# power.net
KiCad netlist of a schematic drawn in Altium Designer
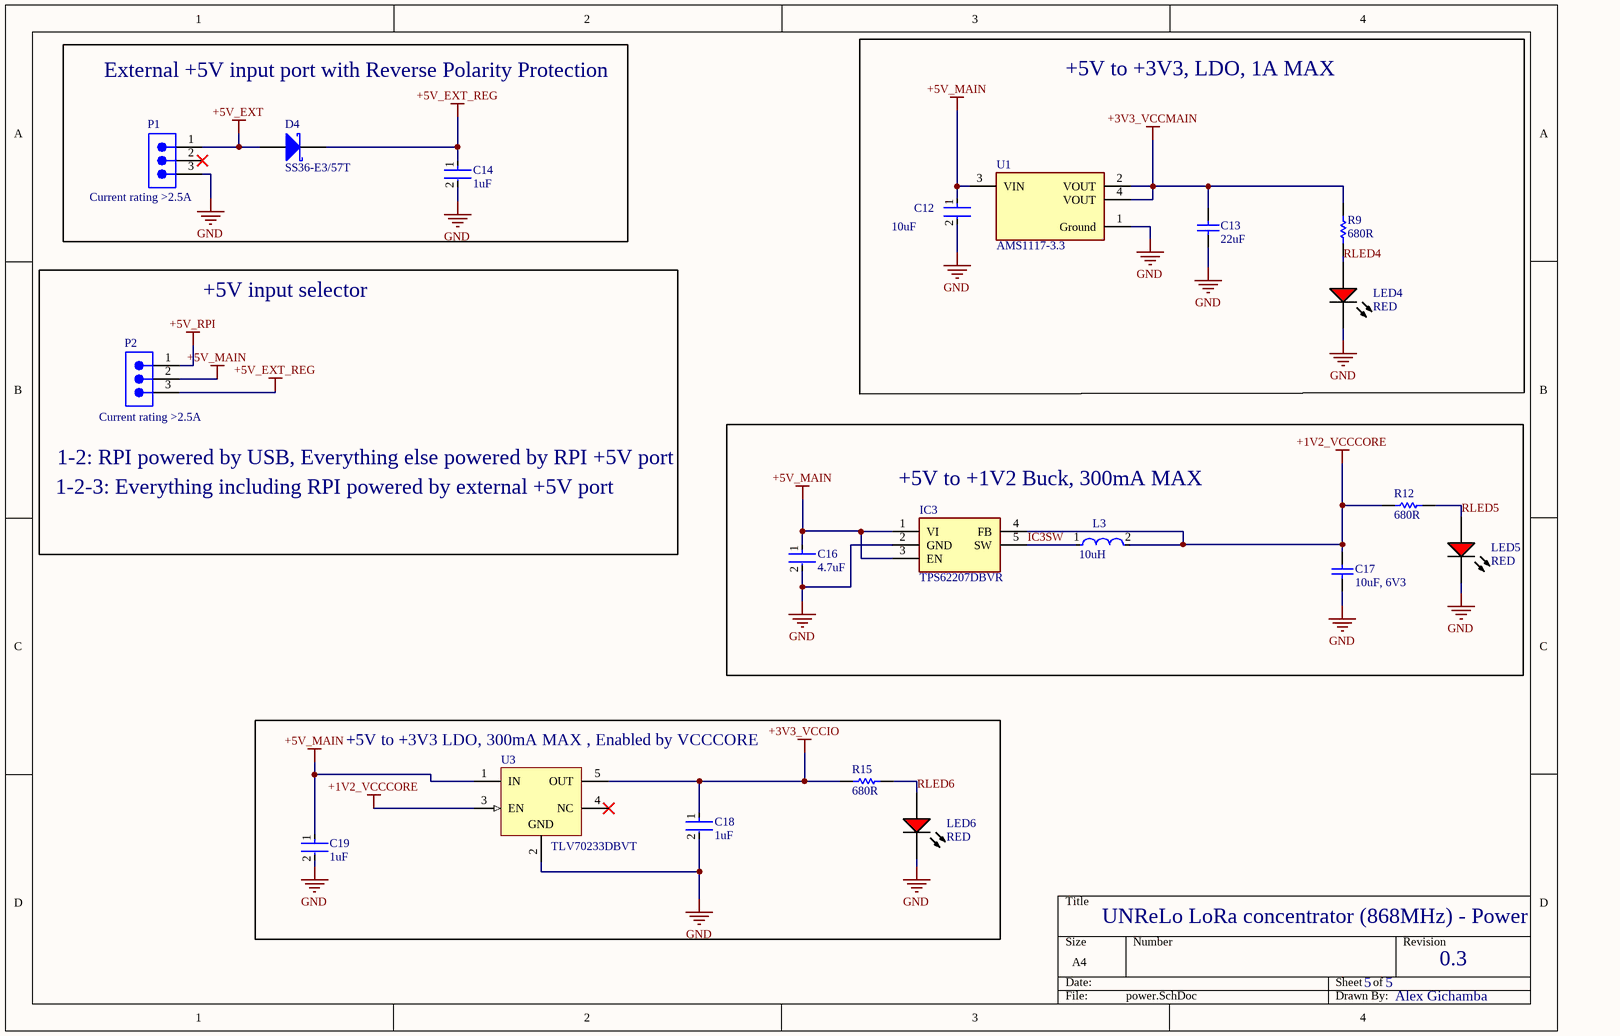
[diagram p0: power.SchDoc]

(export (version "E")
  (design (tool "Eeschema 10.0.6"))
  (components
    (comp (ref "C12")
      (value "10uF")
      (footprint "FP-CL10-IPC_A")
      (description "Cap Ceramic 10uF 6.3V X5R ±20% Pad SMD 0603 +85°C T/R")
      (fields (field (name "VOLTAGE") "6.3V") (field (name "TOLERANCE") "20%"))
      (libsource (lib "Altium Content Vault") (part "b4654b650e69147ec39a6b967a45e02"))
    )
    (comp (ref "C13")
      (value "22uF")
      (footprint "CAPC2013X140X45LL15T25")
      (description "Multi-layer Ceramic Capacitor, 22 uF, -55 to 85 degC, 2-Pin SMD (0805), RoHS, Tape and Reel")
      (fields (field (name "MANUFACTURER") "Samsung Electro-Mechanics") (field (name "TOLERANCE") "±20%"))
      (libsource (lib "Altium Content Vault") (part "CAP-NP-2"))
    )
    (comp (ref "C14")
      (value "1uF")
      (footprint "FP-CL21-IPC_A")
      (description "CL21 Series 0805 1uF 16V ±10% Tolerance X7R Multilayer Ceramic Chip Capacitor")
      (fields (field (name "TOLERANCE") "10%") (field (name "VOLTAGE") "16V"))
      (libsource (lib "Altium Content Vault") (part "b4654b650e69147ec39a6b967a45e02"))
    )
    (comp (ref "C16")
      (value "4.7uF")
      (footprint "FP-CL21-IPC_A")
      (description "CL21 Series 0805 4.7uF 25V ±10% Tolerance X5R Multilayer Ceramic Chip Capacitor")
      (fields (field (name "TOLERANCE") "10%"))
      (libsource (lib "Altium Content Vault") (part "b4654b650e69147ec39a6b967a45e02"))
    )
    (comp (ref "C17")
      (value "10uF, 6V3")
      (footprint "CAPC2013X95X50LL10T25")
      (description "Chip Capacitor, 10 uF, +/- 10%, 6.3 V, -55 to 85 degC, 0805 (2012 Metric), RoHS, Tape and Reel")
      (fields (field (name "TOLERANCE") "±10%") (field (name "MANUFACTURER") "Taiyo Yuden"))
      (libsource (lib "Altium Content Vault") (part "CAP-NP-2"))
    )
    (comp (ref "C18")
      (value "1uF")
      (footprint "FP-CL21-IPC_A")
      (description "CL21 Series 0805 1uF 16V ±10% Tolerance X7R Multilayer Ceramic Chip Capacitor")
      (fields (field (name "TOLERANCE") "10%") (field (name "VOLTAGE") "16V"))
      (libsource (lib "Altium Content Vault") (part "b4654b650e69147ec39a6b967a45e02"))
    )
    (comp (ref "C19")
      (value "1uF")
      (footprint "FP-CL21-IPC_A")
      (description "CL21 Series 0805 1uF 16V ±10% Tolerance X7R Multilayer Ceramic Chip Capacitor")
      (fields (field (name "TOLERANCE") "10%") (field (name "VOLTAGE") "16V"))
      (libsource (lib "Altium Content Vault") (part "b4654b650e69147ec39a6b967a45e02"))
    )
    (comp (ref "D4")
      (value "SS36-E3/57T")
      (footprint "VISH-DO-214AB-2_V")
      (fields (field (name "MANUFACTURER") "Vishay"))
      (libsource (lib "Altium Content Vault") (part "DSKY-AK-2"))
    )
    (comp (ref "IC3")
      (value "TPS62207DBVR")
      (footprint "SamacSys:SOT95P280X145-5N")
      (description "Integrated Circuit")
      (fields (field (name "MOUSER PART NUMBER") "595-TPS62207DBVR"))
      (libsource (lib "*") (part "TPS62207DBVR"))
    )
    (comp (ref "L3")
      (value "10uH")
      (footprint "FP-LQH43CN_03-MFG")
      (description "Wire Wound Ferrite Inductor for Power Lines For Automotive 10μH ±20% 0.1764Ω 1170mA 1812")
      (fields (field (name "TOLERANCE") "5%"))
      (libsource (lib "Altium Content Vault") (part "725321dda6339637d4d059423bc1c3c"))
    )
    (comp (ref "LED4")
      (value "RED")
      (footprint "LTST-C170KRKT_V")
      (description "LED Red, 75 mW, 54 mcd, -55 to 85 degC, 2-Pin SMD, RoHS, Tape and Reel")
      (fields (field (name "MANUFACTURER") "Lite-On"))
      (libsource (lib "Altium Content Vault") (part "LED-RED-AK-2"))
    )
    (comp (ref "LED5")
      (value "RED")
      (footprint "LTST-C170KRKT_V")
      (description "LED Red, 75 mW, 54 mcd, -55 to 85 degC, 2-Pin SMD, RoHS, Tape and Reel")
      (fields (field (name "MANUFACTURER") "Lite-On"))
      (libsource (lib "Altium Content Vault") (part "LED-RED-AK-2"))
    )
    (comp (ref "LED6")
      (value "RED")
      (footprint "LTST-C170KRKT_V")
      (description "LED Red, 75 mW, 54 mcd, -55 to 85 degC, 2-Pin SMD, RoHS, Tape and Reel")
      (fields (field (name "MANUFACTURER") "Lite-On"))
      (libsource (lib "Altium Content Vault") (part "LED-RED-AK-2"))
    )
    (comp (ref "P1")
      (value "Current rating >2.5A")
      (footprint "SMTC-TSW-103-07-X-S")
      (description "0.025\" SQ Post Header, Through-hole, Vertical, -55 to 105 degC, 2.54 mm Pitch, 3-Pin, Male, RoHS")
      (fields (field (name "PARTNUMBER") "TSW-103-07-T-S") (field (name "MANUFACTURER") "Samtec"))
      (libsource (lib "Altium Content Vault") (part "SMTC-TSW-103-X-X-S-X"))
    )
    (comp (ref "P2")
      (value "Current rating >2.5A")
      (footprint "SMTC-TSW-103-07-X-S")
      (description "0.025\" SQ Post Header, Through-hole, Vertical, -55 to 105 degC, 2.54 mm Pitch, 3-Pin, Male, RoHS")
      (fields (field (name "PARTNUMBER") "TSW-103-07-T-S") (field (name "MANUFACTURER") "Samtec"))
      (libsource (lib "Altium Content Vault") (part "SMTC-TSW-103-X-X-S-X"))
    )
    (comp (ref "R9")
      (value "680R")
      (footprint "RESC2013X70X40ML20T20")
      (fields (field (name "PART NUMBER") "ERJ6ENF6800V") (field (name "MANUFACTURER") "Panasonic"))
      (libsource (lib "Altium Content Vault") (part "RES"))
    )
    (comp (ref "R12")
      (value "680R")
      (footprint "RESC2013X70X40ML20T20")
      (fields (field (name "PART NUMBER") "ERJ6ENF6800V") (field (name "MANUFACTURER") "Panasonic"))
      (libsource (lib "Altium Content Vault") (part "RES"))
    )
    (comp (ref "R15")
      (value "680R")
      (footprint "RESC2013X70X40ML20T20")
      (fields (field (name "PART NUMBER") "ERJ6ENF6800V") (field (name "MANUFACTURER") "Panasonic"))
      (libsource (lib "Altium Content Vault") (part "RES"))
    )
    (comp (ref "U1")
      (value "AMS1117-3.3")
      (footprint "FP-AMS1117-IPC_C")
      (description "LDO Voltage Regulators 1A, 3.3V")
      (fields
        (field (name "OCTOPART") "https://octopart.com/ams1117-3.3-advanced+monolithic+systems-25899300")
        (field (name "MANUFACTURER") "Advanced Monolithic Systems")
      )
      (libsource (lib "Altium Content Vault") (part "8bdbb5f8e77002000e30dd2845d0354"))
    )
    (comp (ref "U3")
      (value "TLV70233DBVT")
      (footprint "DBV0005A_N")
      (description "None")
      (libsource (lib "Altium Content Vault") (part "TI-TXX7XXXX-5"))
    )
  )
  (nets
    (net (code "1") (name "+1V2_VCCCORE") (class "Default")
      (node (ref "C17") (pin "1") (pinfunction "1_1") (pintype "passive"))
      (node (ref "IC3") (pin "4") (pinfunction "FB_4") (pintype "passive"))
      (node (ref "L3") (pin "2") (pinfunction "2_2") (pintype "passive"))
      (node (ref "R12") (pin "2") (pinfunction "2_2") (pintype "passive"))
      (node (ref "U3") (pin "3") (pinfunction "EN_3") (pintype "input"))
    )
    (net (code "2") (name "+3V3_VCCIO") (class "Default")
      (node (ref "C18") (pin "1") (pinfunction "1_1") (pintype "passive"))
      (node (ref "R15") (pin "2") (pinfunction "2_2") (pintype "passive"))
      (node (ref "U3") (pin "5") (pinfunction "OUT_5") (pintype "power_in"))
    )
    (net (code "3") (name "+3V3_VCCMAIN") (class "Default")
      (node (ref "C13") (pin "2") (pinfunction "2_2") (pintype "passive"))
      (node (ref "R9") (pin "2") (pinfunction "2_2") (pintype "passive"))
      (node (ref "U1") (pin "2") (pinfunction "VOUT_2") (pintype "passive"))
      (node (ref "U1") (pin "4") (pinfunction "VOUT_4") (pintype "passive"))
    )
    (net (code "4") (name "+5V_EXT") (class "Default")
      (node (ref "D4") (pin "1") (pinfunction "A_1") (pintype "passive"))
      (node (ref "P1") (pin "1") (pinfunction "1_1") (pintype "passive"))
    )
    (net (code "5") (name "+5V_EXT_REG") (class "Default")
      (node (ref "C14") (pin "1") (pinfunction "1_1") (pintype "passive"))
      (node (ref "D4") (pin "2") (pinfunction "K_2") (pintype "passive"))
      (node (ref "P2") (pin "3") (pinfunction "3_3") (pintype "passive"))
    )
    (net (code "6") (name "+5V_MAIN") (class "Default")
      (node (ref "C12") (pin "1") (pinfunction "1_1") (pintype "passive"))
      (node (ref "C16") (pin "1") (pinfunction "1_1") (pintype "passive"))
      (node (ref "C19") (pin "1") (pinfunction "1_1") (pintype "passive"))
      (node (ref "IC3") (pin "1") (pinfunction "VI_1") (pintype "passive"))
      (node (ref "IC3") (pin "3") (pinfunction "EN_3") (pintype "passive"))
      (node (ref "P2") (pin "2") (pinfunction "2_2") (pintype "passive"))
      (node (ref "U1") (pin "3") (pinfunction "VIN_3") (pintype "power_in"))
      (node (ref "U3") (pin "1") (pinfunction "IN_1") (pintype "power_in"))
    )
    (net (code "7") (name "+5V_RPI") (class "Default")
      (node (ref "P2") (pin "1") (pinfunction "1_1") (pintype "passive"))
    )
    (net (code "8") (name "/IC3SW") (class "Default")
      (node (ref "IC3") (pin "5") (pinfunction "SW_5") (pintype "passive"))
      (node (ref "L3") (pin "1") (pinfunction "1_1") (pintype "passive"))
    )
    (net (code "9") (name "/RLED4") (class "Default")
      (node (ref "LED4") (pin "1") (pinfunction "A_1") (pintype "passive"))
      (node (ref "R9") (pin "1") (pinfunction "1_1") (pintype "passive"))
    )
    (net (code "10") (name "/RLED5") (class "Default")
      (node (ref "LED5") (pin "1") (pinfunction "A_1") (pintype "passive"))
      (node (ref "R12") (pin "1") (pinfunction "1_1") (pintype "passive"))
    )
    (net (code "11") (name "/RLED6") (class "Default")
      (node (ref "LED6") (pin "1") (pinfunction "A_1") (pintype "passive"))
      (node (ref "R15") (pin "1") (pinfunction "1_1") (pintype "passive"))
    )
    (net (code "12") (name "GND") (class "Default")
      (node (ref "C12") (pin "2") (pinfunction "2_2") (pintype "passive"))
      (node (ref "C13") (pin "1") (pinfunction "1_1") (pintype "passive"))
      (node (ref "C14") (pin "2") (pinfunction "2_2") (pintype "passive"))
      (node (ref "C16") (pin "2") (pinfunction "2_2") (pintype "passive"))
      (node (ref "C17") (pin "2") (pinfunction "2_2") (pintype "passive"))
      (node (ref "C18") (pin "2") (pinfunction "2_2") (pintype "passive"))
      (node (ref "C19") (pin "2") (pinfunction "2_2") (pintype "passive"))
      (node (ref "IC3") (pin "2") (pinfunction "GND_2") (pintype "passive"))
      (node (ref "LED4") (pin "2") (pinfunction "K_2") (pintype "passive"))
      (node (ref "LED5") (pin "2") (pinfunction "K_2") (pintype "passive"))
      (node (ref "LED6") (pin "2") (pinfunction "K_2") (pintype "passive"))
      (node (ref "P1") (pin "3") (pinfunction "3_3") (pintype "passive"))
      (node (ref "U1") (pin "1") (pinfunction "Ground_1") (pintype "power_in"))
      (node (ref "U3") (pin "2") (pinfunction "GND_2") (pintype "power_in"))
    )
    (net (code "13") (name "unconnected-(P1-Pad2)") (class "Default")
      (node (ref "P1") (pin "2") (pinfunction "2_2") (pintype "passive+no_connect"))
    )
    (net (code "14") (name "unconnected-(U3-NC-Pad4)") (class "Default")
      (node (ref "U3") (pin "4") (pinfunction "NC_4") (pintype "passive+no_connect"))
    )
  )
)
